# rev1.net
KiCad netlist of a schematic drawn in EAGLE
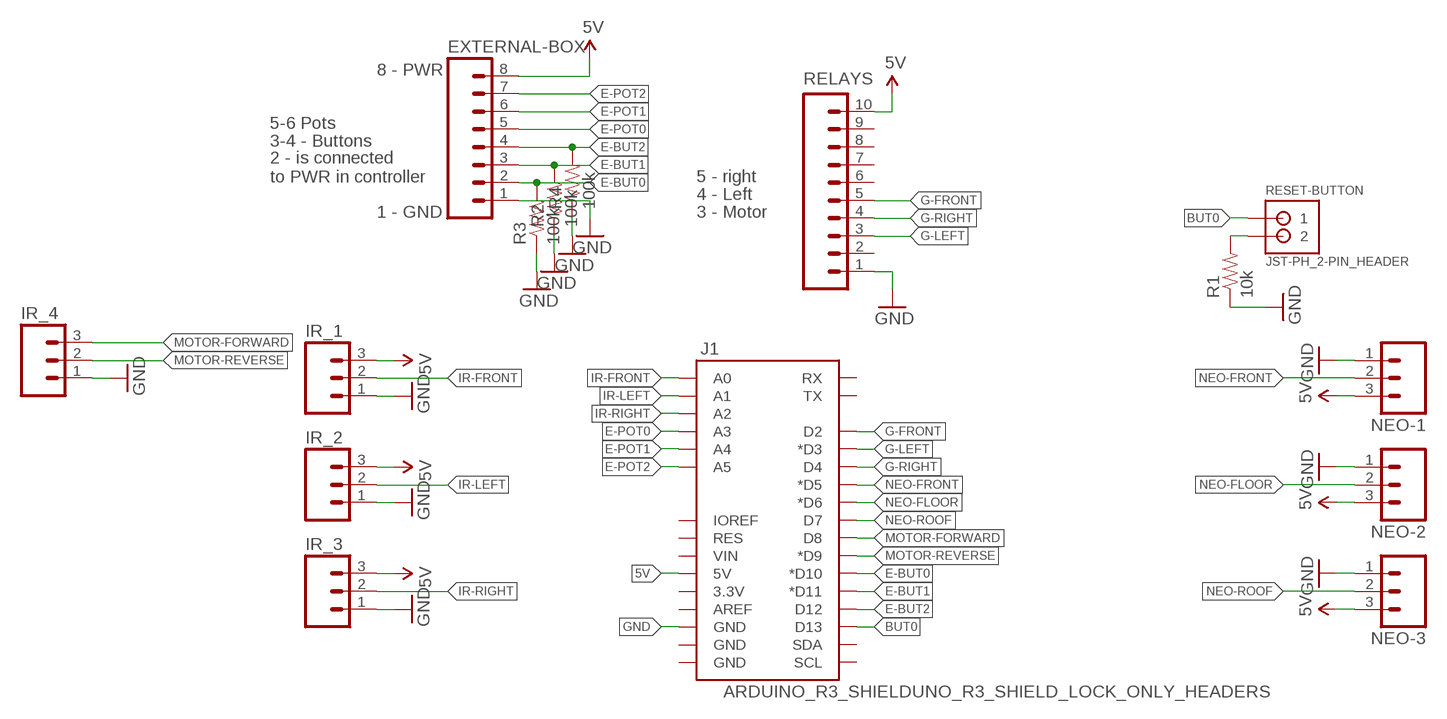
[diagram p0: schematic, sheet 1]

(export (version "E")
  (design (tool "Eeschema 10.0.6"))
  (components
    (comp (ref "EXTERNAL-BOX")
      (value "M08NO_SILK")
      (footprint "eagle-import:1X08_PIN1_NO_SILK")
      (libsource (lib "eagle-import") (part "M08NO_SILK"))
    )
    (comp (ref "IR_1")
      (value "M03POLAR")
      (footprint "eagle-import:MOLEX-1X3")
      (libsource (lib "eagle-import") (part "M03POLAR"))
    )
    (comp (ref "IR_2")
      (value "M03POLAR")
      (footprint "eagle-import:MOLEX-1X3")
      (libsource (lib "eagle-import") (part "M03POLAR"))
    )
    (comp (ref "IR_3")
      (value "M03POLAR")
      (footprint "eagle-import:MOLEX-1X3")
      (libsource (lib "eagle-import") (part "M03POLAR"))
    )
    (comp (ref "IR_4")
      (value "M03POLAR")
      (footprint "eagle-import:MOLEX-1X3")
      (libsource (lib "eagle-import") (part "M03POLAR"))
    )
    (comp (ref "J1")
      (value "ARDUINO_R3_SHIELDUNO_R3_SHIELD_LOCK_ONLY_HEADERS")
      (footprint "eagle-import:UNO_R3_SHIELD_ONLY_HEADERS")
      (libsource (lib "eagle-import") (part "ARDUINO_R3_SHIELDUNO_R3_SHIELD_LOCK_ONLY_HEADERS"))
    )
    (comp (ref "NEO-1")
      (value "M03POLAR")
      (footprint "eagle-import:MOLEX-1X3")
      (libsource (lib "eagle-import") (part "M03POLAR"))
    )
    (comp (ref "NEO-2")
      (value "M03POLAR")
      (footprint "eagle-import:MOLEX-1X3")
      (libsource (lib "eagle-import") (part "M03POLAR"))
    )
    (comp (ref "NEO-3")
      (value "M03POLAR")
      (footprint "eagle-import:MOLEX-1X3")
      (libsource (lib "eagle-import") (part "M03POLAR"))
    )
    (comp (ref "R1")
      (value "10k")
      (footprint "eagle-import:AXIAL-0.3")
      (libsource (lib "eagle-import") (part "RESISTORAXIAL-0.3"))
    )
    (comp (ref "R2")
      (value "100k")
      (footprint "eagle-import:AXIAL-0.3")
      (libsource (lib "eagle-import") (part "RESISTORAXIAL-0.3"))
    )
    (comp (ref "R3")
      (value "100k")
      (footprint "eagle-import:AXIAL-0.3")
      (libsource (lib "eagle-import") (part "RESISTORAXIAL-0.3"))
    )
    (comp (ref "R4")
      (value "100k")
      (footprint "eagle-import:AXIAL-0.3")
      (libsource (lib "eagle-import") (part "RESISTORAXIAL-0.3"))
    )
    (comp (ref "RELAYS")
      (value "M10NO_SILK_PTH_FEMALE")
      (footprint "eagle-import:1X10_NO_SILK")
      (libsource (lib "eagle-import") (part "M10NO_SILK_PTH_FEMALE"))
    )
    (comp (ref "RESET-BUTTON")
      (value "JST-PH_2-PIN_HEADER")
      (footprint "eagle-import:JST_B2B-PH_HEADER")
      (libsource (lib "eagle-import") (part "JST-PH_2-PIN_HEADER"))
    )
  )
  (nets
    (net (code "1") (name "5V") (class "Default")
      (node (ref "EXTERNAL-BOX") (pin "8") (pinfunction "8_8") (pintype "passive"))
      (node (ref "IR_1") (pin "3") (pinfunction "3_3") (pintype "passive"))
      (node (ref "IR_2") (pin "3") (pinfunction "3_3") (pintype "passive"))
      (node (ref "IR_3") (pin "3") (pinfunction "3_3") (pintype "passive"))
      (node (ref "J1") (pin "5V") (pinfunction "5V_5V") (pintype "bidirectional"))
      (node (ref "NEO-1") (pin "3") (pinfunction "3_3") (pintype "passive"))
      (node (ref "NEO-2") (pin "3") (pinfunction "3_3") (pintype "passive"))
      (node (ref "NEO-3") (pin "3") (pinfunction "3_3") (pintype "passive"))
      (node (ref "RELAYS") (pin "10") (pinfunction "10_10") (pintype "passive"))
    )
    (net (code "2") (name "BUT0") (class "Default")
      (node (ref "J1") (pin "D13") (pinfunction "D13_D13") (pintype "bidirectional"))
      (node (ref "RESET-BUTTON") (pin "P1") (pinfunction "1_P1") (pintype "bidirectional"))
    )
    (net (code "3") (name "E-BUT0") (class "Default")
      (node (ref "EXTERNAL-BOX") (pin "2") (pinfunction "2_2") (pintype "passive"))
      (node (ref "J1") (pin "D10") (pinfunction "*D10_D10") (pintype "bidirectional"))
      (node (ref "R3") (pin "P$2") (pinfunction "2_P$2") (pintype "passive"))
    )
    (net (code "4") (name "E-BUT1") (class "Default")
      (node (ref "EXTERNAL-BOX") (pin "3") (pinfunction "3_3") (pintype "passive"))
      (node (ref "J1") (pin "D11") (pinfunction "*D11_D11") (pintype "bidirectional"))
      (node (ref "R2") (pin "P$2") (pinfunction "2_P$2") (pintype "passive"))
    )
    (net (code "5") (name "E-BUT2") (class "Default")
      (node (ref "EXTERNAL-BOX") (pin "4") (pinfunction "4_4") (pintype "passive"))
      (node (ref "J1") (pin "D12") (pinfunction "D12_D12") (pintype "bidirectional"))
      (node (ref "R4") (pin "P$2") (pinfunction "2_P$2") (pintype "passive"))
    )
    (net (code "6") (name "E-POT0") (class "Default")
      (node (ref "EXTERNAL-BOX") (pin "5") (pinfunction "5_5") (pintype "passive"))
      (node (ref "J1") (pin "A3") (pinfunction "A3_A3") (pintype "bidirectional"))
    )
    (net (code "7") (name "E-POT1") (class "Default")
      (node (ref "EXTERNAL-BOX") (pin "6") (pinfunction "6_6") (pintype "passive"))
      (node (ref "J1") (pin "A4") (pinfunction "A4_A4") (pintype "bidirectional"))
    )
    (net (code "8") (name "E-POT2") (class "Default")
      (node (ref "EXTERNAL-BOX") (pin "7") (pinfunction "7_7") (pintype "passive"))
      (node (ref "J1") (pin "A5") (pinfunction "A5_A5") (pintype "bidirectional"))
    )
    (net (code "9") (name "G-FRONT") (class "Default")
      (node (ref "J1") (pin "D2") (pinfunction "D2_D2") (pintype "bidirectional"))
      (node (ref "RELAYS") (pin "5") (pinfunction "5_5") (pintype "passive"))
    )
    (net (code "10") (name "G-LEFT") (class "Default")
      (node (ref "J1") (pin "D3") (pinfunction "*D3_D3") (pintype "bidirectional"))
      (node (ref "RELAYS") (pin "3") (pinfunction "3_3") (pintype "passive"))
    )
    (net (code "11") (name "G-RIGHT") (class "Default")
      (node (ref "J1") (pin "D4") (pinfunction "D4_D4") (pintype "bidirectional"))
      (node (ref "RELAYS") (pin "4") (pinfunction "4_4") (pintype "passive"))
    )
    (net (code "12") (name "GND") (class "Default")
      (node (ref "EXTERNAL-BOX") (pin "1") (pinfunction "1_1") (pintype "passive"))
      (node (ref "IR_1") (pin "1") (pinfunction "1_1") (pintype "passive"))
      (node (ref "IR_2") (pin "1") (pinfunction "1_1") (pintype "passive"))
      (node (ref "IR_3") (pin "1") (pinfunction "1_1") (pintype "passive"))
      (node (ref "IR_4") (pin "1") (pinfunction "1_1") (pintype "passive"))
      (node (ref "J1") (pin "GND@2") (pinfunction "GND_GND@2") (pintype "bidirectional"))
      (node (ref "NEO-1") (pin "1") (pinfunction "1_1") (pintype "passive"))
      (node (ref "NEO-2") (pin "1") (pinfunction "1_1") (pintype "passive"))
      (node (ref "NEO-3") (pin "1") (pinfunction "1_1") (pintype "passive"))
      (node (ref "R1") (pin "P$1") (pinfunction "1_P$1") (pintype "passive"))
      (node (ref "R2") (pin "P$1") (pinfunction "1_P$1") (pintype "passive"))
      (node (ref "R3") (pin "P$1") (pinfunction "1_P$1") (pintype "passive"))
      (node (ref "R4") (pin "P$1") (pinfunction "1_P$1") (pintype "passive"))
      (node (ref "RELAYS") (pin "1") (pinfunction "1_1") (pintype "passive"))
    )
    (net (code "13") (name "IR-FRONT") (class "Default")
      (node (ref "IR_1") (pin "2") (pinfunction "2_2") (pintype "passive"))
      (node (ref "J1") (pin "A0") (pinfunction "A0_A0") (pintype "bidirectional"))
    )
    (net (code "14") (name "IR-LEFT") (class "Default")
      (node (ref "IR_2") (pin "2") (pinfunction "2_2") (pintype "passive"))
      (node (ref "J1") (pin "A1") (pinfunction "A1_A1") (pintype "bidirectional"))
    )
    (net (code "15") (name "IR-RIGHT") (class "Default")
      (node (ref "IR_3") (pin "2") (pinfunction "2_2") (pintype "passive"))
      (node (ref "J1") (pin "A2") (pinfunction "A2_A2") (pintype "bidirectional"))
    )
    (net (code "16") (name "MOTOR-FORWARD") (class "Default")
      (node (ref "IR_4") (pin "3") (pinfunction "3_3") (pintype "passive"))
      (node (ref "J1") (pin "D8") (pinfunction "D8_D8") (pintype "bidirectional"))
    )
    (net (code "17") (name "MOTOR-REVERSE") (class "Default")
      (node (ref "IR_4") (pin "2") (pinfunction "2_2") (pintype "passive"))
      (node (ref "J1") (pin "D9") (pinfunction "*D9_D9") (pintype "bidirectional"))
    )
    (net (code "18") (name "NEO-FLOOR") (class "Default")
      (node (ref "J1") (pin "D6") (pinfunction "*D6_D6") (pintype "bidirectional"))
      (node (ref "NEO-2") (pin "2") (pinfunction "2_2") (pintype "passive"))
    )
    (net (code "19") (name "NEO-FRONT") (class "Default")
      (node (ref "J1") (pin "D5") (pinfunction "*D5_D5") (pintype "bidirectional"))
      (node (ref "NEO-1") (pin "2") (pinfunction "2_2") (pintype "passive"))
    )
    (net (code "20") (name "NEO-ROOF") (class "Default")
      (node (ref "J1") (pin "D7") (pinfunction "D7_D7") (pintype "bidirectional"))
      (node (ref "NEO-3") (pin "2") (pinfunction "2_2") (pintype "passive"))
    )
    (net (code "21") (name "Net-(R1-2)") (class "Default")
      (node (ref "R1") (pin "P$2") (pinfunction "2_P$2") (pintype "passive"))
      (node (ref "RESET-BUTTON") (pin "P2") (pinfunction "2_P2") (pintype "bidirectional"))
    )
    (net (code "22") (name "unconnected-(J1-GND-PadGND@0)") (class "Default")
      (node (ref "J1") (pin "GND@0") (pinfunction "GND_GND@0") (pintype "bidirectional"))
    )
    (net (code "23") (name "unconnected-(J1-GND-PadGND@1)") (class "Default")
      (node (ref "J1") (pin "GND@1") (pinfunction "GND_GND@1") (pintype "bidirectional"))
    )
    (net (code "24") (name "unconnected-(J1-Pad3.3V)") (class "Default")
      (node (ref "J1") (pin "3.3V") (pinfunction "3.3V_3.3V") (pintype "bidirectional"))
    )
    (net (code "25") (name "unconnected-(J1-PadAREF)") (class "Default")
      (node (ref "J1") (pin "AREF") (pinfunction "AREF_AREF") (pintype "bidirectional"))
    )
    (net (code "26") (name "unconnected-(J1-PadIOREF)") (class "Default")
      (node (ref "J1") (pin "IOREF") (pinfunction "IOREF_IOREF") (pintype "bidirectional"))
    )
    (net (code "27") (name "unconnected-(J1-PadRES)") (class "Default")
      (node (ref "J1") (pin "RES") (pinfunction "RES_RES") (pintype "bidirectional"))
    )
    (net (code "28") (name "unconnected-(J1-PadRX)") (class "Default")
      (node (ref "J1") (pin "RX") (pinfunction "RX_RX") (pintype "bidirectional"))
    )
    (net (code "29") (name "unconnected-(J1-PadSCL)") (class "Default")
      (node (ref "J1") (pin "SCL") (pinfunction "SCL_SCL") (pintype "bidirectional"))
    )
    (net (code "30") (name "unconnected-(J1-PadSDA)") (class "Default")
      (node (ref "J1") (pin "SDA") (pinfunction "SDA_SDA") (pintype "bidirectional"))
    )
    (net (code "31") (name "unconnected-(J1-PadTX)") (class "Default")
      (node (ref "J1") (pin "TX") (pinfunction "TX_TX") (pintype "bidirectional"))
    )
    (net (code "32") (name "unconnected-(J1-PadVIN)") (class "Default")
      (node (ref "J1") (pin "VIN") (pinfunction "VIN_VIN") (pintype "bidirectional"))
    )
    (net (code "33") (name "unconnected-(RELAYS-Pad2)") (class "Default")
      (node (ref "RELAYS") (pin "2") (pinfunction "2_2") (pintype "passive"))
    )
    (net (code "34") (name "unconnected-(RELAYS-Pad6)") (class "Default")
      (node (ref "RELAYS") (pin "6") (pinfunction "6_6") (pintype "passive"))
    )
    (net (code "35") (name "unconnected-(RELAYS-Pad7)") (class "Default")
      (node (ref "RELAYS") (pin "7") (pinfunction "7_7") (pintype "passive"))
    )
    (net (code "36") (name "unconnected-(RELAYS-Pad8)") (class "Default")
      (node (ref "RELAYS") (pin "8") (pinfunction "8_8") (pintype "passive"))
    )
    (net (code "37") (name "unconnected-(RELAYS-Pad9)") (class "Default")
      (node (ref "RELAYS") (pin "9") (pinfunction "9_9") (pintype "passive"))
    )
  )
)
